# Sheet1.net
KiCad netlist of a schematic drawn in Altium Designer
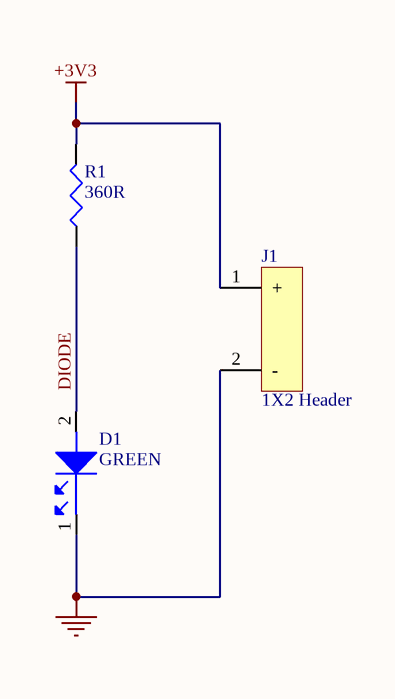
[diagram p0: Sheet1.SchDoc]

(export (version "E")
  (design (tool "Eeschema 10.0.6"))
  (components
    (comp (ref "D1")
      (value "GREEN")
      (footprint "LED0603_GREEN")
      (description "LED GREEN ESS II SMD")
      (fields
        (field (name "MANUFACTURER") "Panasonic SSG")
        (field (name "MANUFACTURER PART NUMBER") "LNJ337W83RA")
      )
      (libsource (lib "Schlib1") (part "LNJ337W83RA"))
    )
    (comp (ref "J1")
      (value "1X2 Header")
      (footprint "HEADER 1X2")
      (description "CONN HEADER VERT 2POS 2.54MM")
      (fields (field (name "MANUFACTURER") "Molex") (field (name "MANUFACTURER PART NUMBER") "22-29-2021"))
      (libsource (lib "Schlib1") (part "22-29-2021"))
    )
    (comp (ref "R1")
      (value "360R")
      (footprint "R0805")
      (description "Res Thick Film 0805 360 Ohm 1% 0.125W(1/8W) ±100ppm/C Molded SMD Automotive Paper T/R")
      (fields
        (field (name "MANUFACTURER") "Vishay")
        (field (name "MANUFACTURER PART NUMBER") "CRCW0805360RFKEA")
      )
      (libsource (lib "Schlib1") (part "CRCW0805360RFKEA"))
    )
  )
  (nets
    (net (code "1") (name "+3V3") (class "Default")
      (node (ref "J1") (pin "1") (pinfunction "+_1") (pintype "passive"))
      (node (ref "R1") (pin "2") (pinfunction "2_2") (pintype "passive"))
    )
    (net (code "2") (name "/DIODE") (class "Default")
      (node (ref "D1") (pin "2") (pinfunction "2_2") (pintype "passive"))
      (node (ref "R1") (pin "1") (pinfunction "1_1") (pintype "passive"))
    )
    (net (code "3") (name "GND") (class "Default")
      (node (ref "D1") (pin "1") (pinfunction "1_1") (pintype "passive"))
      (node (ref "J1") (pin "2") (pinfunction "-_2") (pintype "passive"))
    )
  )
)
